# Sch_ma_Global.net
KiCad netlist of a schematic drawn in Altium Designer
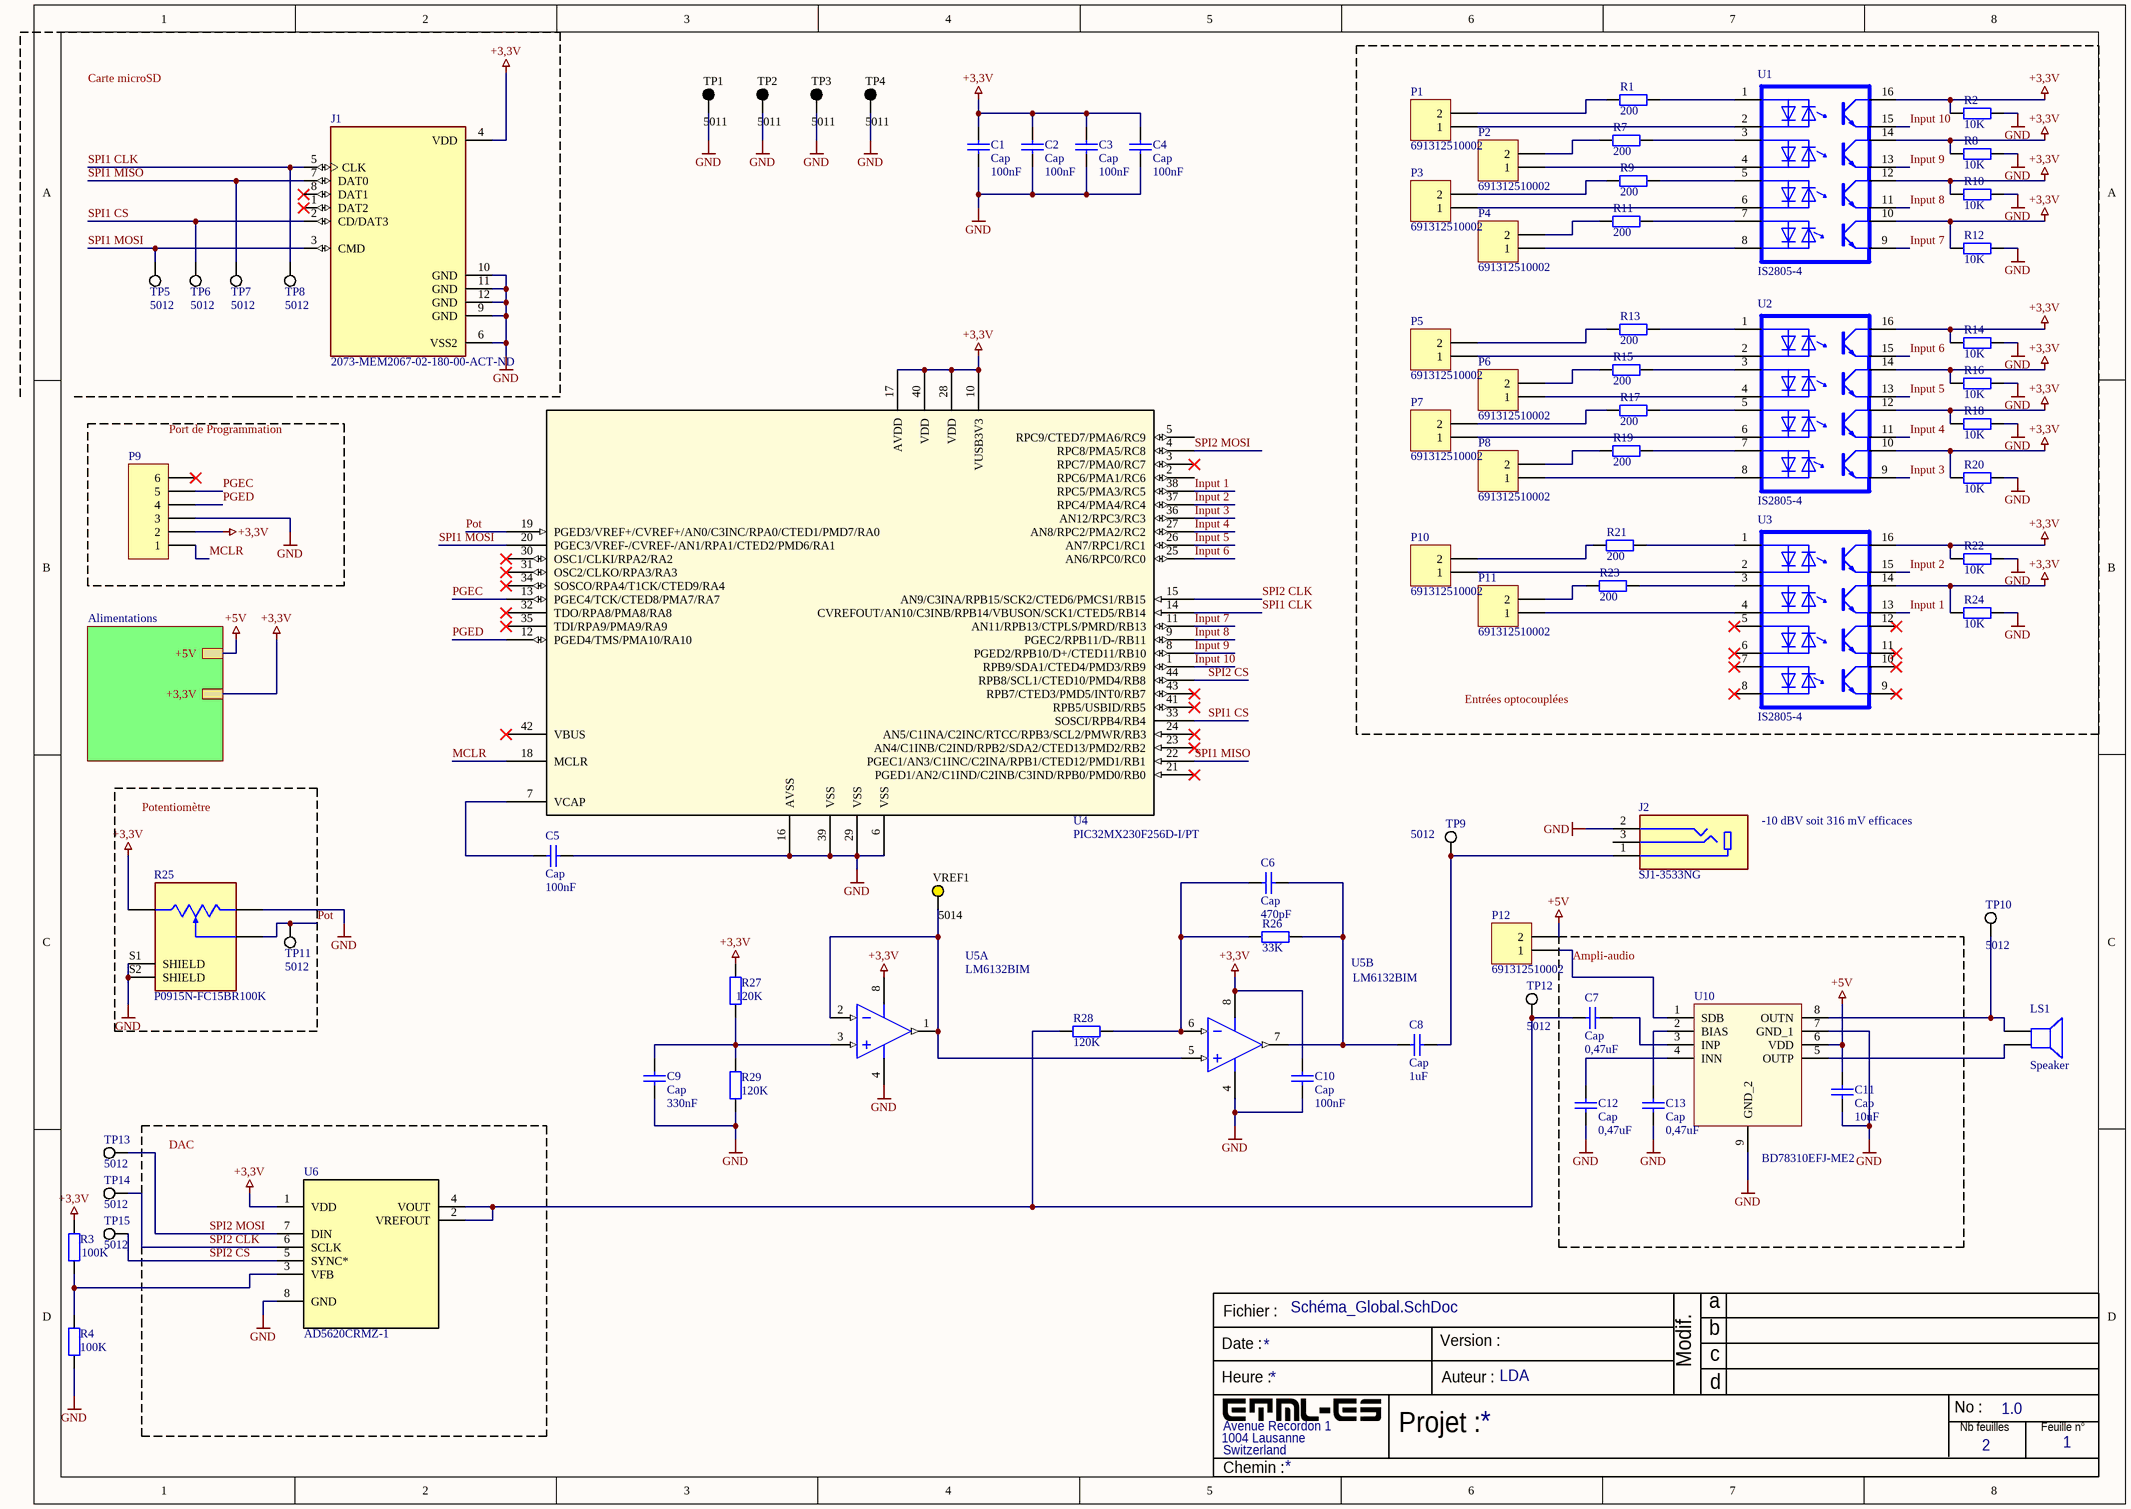
[diagram p0: Schéma_Global.SchDoc]

(export (version "E")
  (design (tool "Eeschema 10.0.6"))
  (components
    (comp (ref "C1")
      (value "Cap")
      (footprint "C0805")
      (description "Capacitor")
      (fields (field (name "ALTIUM_VALUE") "100nF") (field (name "PUBLISHER") "Altium Limited"))
      (libsource (lib "Miscellaneous Devices") (part "Cap"))
    )
    (comp (ref "C2")
      (value "Cap")
      (footprint "C0805")
      (description "Capacitor")
      (fields (field (name "ALTIUM_VALUE") "100nF") (field (name "PUBLISHER") "Altium Limited"))
      (libsource (lib "Miscellaneous Devices") (part "Cap"))
    )
    (comp (ref "C3")
      (value "Cap")
      (footprint "C0805")
      (description "Capacitor")
      (fields (field (name "ALTIUM_VALUE") "100nF") (field (name "PUBLISHER") "Altium Limited"))
      (libsource (lib "Miscellaneous Devices") (part "Cap"))
    )
    (comp (ref "C4")
      (value "Cap")
      (footprint "C0805")
      (description "Capacitor")
      (fields (field (name "ALTIUM_VALUE") "100nF") (field (name "PUBLISHER") "Altium Limited"))
      (libsource (lib "Miscellaneous Devices") (part "Cap"))
    )
    (comp (ref "C5")
      (value "Cap")
      (footprint "C0805")
      (description "Capacitor")
      (fields (field (name "ALTIUM_VALUE") "100nF") (field (name "PUBLISHER") "Altium Limited"))
      (libsource (lib "Miscellaneous Devices") (part "Cap"))
    )
    (comp (ref "C6")
      (value "Cap")
      (footprint "C0805")
      (description "Capacitor")
      (fields (field (name "ALTIUM_VALUE") "470pF") (field (name "PUBLISHER") "Altium Limited"))
      (libsource (lib "Miscellaneous Devices") (part "Cap"))
    )
    (comp (ref "C7")
      (value "Cap")
      (footprint "C0805")
      (description "Capacitor")
      (fields (field (name "ALTIUM_VALUE") "0,47uF") (field (name "PUBLISHER") "Altium Limited"))
      (libsource (lib "Miscellaneous Devices") (part "Cap"))
    )
    (comp (ref "C8")
      (value "Cap")
      (footprint "C0805")
      (description "Capacitor")
      (fields (field (name "ALTIUM_VALUE") "1uF") (field (name "PUBLISHER") "Altium Limited"))
      (libsource (lib "Miscellaneous Devices") (part "Cap"))
    )
    (comp (ref "C9")
      (value "Cap")
      (footprint "C0805")
      (description "Capacitor")
      (fields (field (name "ALTIUM_VALUE") "330nF") (field (name "PUBLISHER") "Altium Limited"))
      (libsource (lib "Miscellaneous Devices") (part "Cap"))
    )
    (comp (ref "C10")
      (value "Cap")
      (footprint "C0805")
      (description "Capacitor")
      (fields (field (name "ALTIUM_VALUE") "100nF") (field (name "PUBLISHER") "Altium Limited"))
      (libsource (lib "Miscellaneous Devices") (part "Cap"))
    )
    (comp (ref "C11")
      (value "Cap")
      (footprint "C0805")
      (description "Capacitor")
      (fields (field (name "ALTIUM_VALUE") "10uF") (field (name "PUBLISHER") "Altium Limited"))
      (libsource (lib "Miscellaneous Devices") (part "Cap"))
    )
    (comp (ref "C12")
      (value "Cap")
      (footprint "C0805")
      (description "Capacitor")
      (fields (field (name "ALTIUM_VALUE") "0,47uF") (field (name "PUBLISHER") "Altium Limited"))
      (libsource (lib "Miscellaneous Devices") (part "Cap"))
    )
    (comp (ref "C13")
      (value "Cap")
      (footprint "C0805")
      (description "Capacitor")
      (fields (field (name "ALTIUM_VALUE") "0,47uF") (field (name "PUBLISHER") "Altium Limited"))
      (libsource (lib "Miscellaneous Devices") (part "Cap"))
    )
    (comp (ref "J1")
      (value "2073-MEM2067-02-180-00-ACT-ND")
      (footprint "GCT_MEM2067-02-180-00-A_REVB")
      (description "2 In 1 Connector Sd+mmc")
      (fields (field (name "MP") "GMC020080HR") (field (name "MF") "Amphenol ICC (Commercial Products)"))
      (libsource (lib "2227_BoiteBruitage") (part "GMC020080HR"))
    )
    (comp (ref "J2")
      (value "SJ1-3533NG")
      (footprint "CUI_SJ1-3533NG")
      (description "3.5 mm Right-Angle Stereo Jack, 3 Pin PCB Mount, Isolated Ground")
      (fields (field (name "MF") "{'manufacturer': u'CUI'}"))
      (libsource (lib "2227_BoiteBruitage") (part "SJ1-3533NG"))
    )
    (comp (ref "LS1")
      (value "Speaker")
      (footprint "PIN2")
      (description "Loudspeaker")
      (fields (field (name "PUBLISHER") "Altium Limited"))
      (libsource (lib "Miscellaneous Devices") (part "Speaker"))
    )
    (comp (ref "P1")
      (value "691312510002")
      (footprint "691312710002")
      (description "Header, 2-Pin")
      (fields (field (name "PUBLISHER") "Altium Limited"))
      (libsource (lib "Miscellaneous Connectors") (part "MHDR1X2"))
    )
    (comp (ref "P2")
      (value "691312510002")
      (footprint "691312710002")
      (description "Header, 2-Pin")
      (fields (field (name "PUBLISHER") "Altium Limited"))
      (libsource (lib "Miscellaneous Connectors") (part "MHDR1X2"))
    )
    (comp (ref "P3")
      (value "691312510002")
      (footprint "691312710002")
      (description "Header, 2-Pin")
      (fields (field (name "PUBLISHER") "Altium Limited"))
      (libsource (lib "Miscellaneous Connectors") (part "MHDR1X2"))
    )
    (comp (ref "P4")
      (value "691312510002")
      (footprint "691312710002")
      (description "Header, 2-Pin")
      (fields (field (name "PUBLISHER") "Altium Limited"))
      (libsource (lib "Miscellaneous Connectors") (part "MHDR1X2"))
    )
    (comp (ref "P5")
      (value "691312510002")
      (footprint "691312710002")
      (description "Header, 2-Pin")
      (fields (field (name "PUBLISHER") "Altium Limited"))
      (libsource (lib "Miscellaneous Connectors") (part "MHDR1X2"))
    )
    (comp (ref "P6")
      (value "691312510002")
      (footprint "691312710002")
      (description "Header, 2-Pin")
      (fields (field (name "PUBLISHER") "Altium Limited"))
      (libsource (lib "Miscellaneous Connectors") (part "MHDR1X2"))
    )
    (comp (ref "P7")
      (value "691312510002")
      (footprint "691312710002")
      (description "Header, 2-Pin")
      (fields (field (name "PUBLISHER") "Altium Limited"))
      (libsource (lib "Miscellaneous Connectors") (part "MHDR1X2"))
    )
    (comp (ref "P8")
      (value "691312510002")
      (footprint "691312710002")
      (description "Header, 2-Pin")
      (fields (field (name "PUBLISHER") "Altium Limited"))
      (libsource (lib "Miscellaneous Connectors") (part "MHDR1X2"))
    )
    (comp (ref "P9")
      (value "76384-406LF")
      (footprint "HDR1X6")
      (description "Header, 6-Pin")
      (fields (field (name "PUBLISHER") "Altium Limited"))
      (libsource (lib "Miscellaneous Connectors") (part "Header 6"))
    )
    (comp (ref "P10")
      (value "691312510002")
      (footprint "691312710002")
      (description "Header, 2-Pin")
      (fields (field (name "PUBLISHER") "Altium Limited"))
      (libsource (lib "Miscellaneous Connectors") (part "MHDR1X2"))
    )
    (comp (ref "P11")
      (value "691312510002")
      (footprint "691312710002")
      (description "Header, 2-Pin")
      (fields (field (name "PUBLISHER") "Altium Limited"))
      (libsource (lib "Miscellaneous Connectors") (part "MHDR1X2"))
    )
    (comp (ref "P12")
      (value "691312510002")
      (footprint "MHDR1X2")
      (description "Header, 2-Pin")
      (fields (field (name "PUBLISHER") "Altium Limited"))
      (libsource (lib "Miscellaneous Connectors") (part "MHDR1X2"))
    )
    (comp (ref "R1")
      (value "200")
      (footprint "C1206")
      (description "Resistor")
      (fields (field (name "Comment") "Res2") (field (name "PUBLISHER") "Altium Limited"))
      (libsource (lib "Miscellaneous Devices") (part "Res2"))
    )
    (comp (ref "R2")
      (value "10K")
      (footprint "C1206")
      (description "Resistor")
      (fields (field (name "Comment") "Res2") (field (name "PUBLISHER") "Altium Limited"))
      (libsource (lib "Miscellaneous Devices") (part "Res2"))
    )
    (comp (ref "R3")
      (value "100K")
      (footprint "C1206")
      (description "Resistor")
      (fields (field (name "Comment") "Res2") (field (name "PUBLISHER") "Altium Limited"))
      (libsource (lib "") (part "Res2_1"))
    )
    (comp (ref "R4")
      (value "100K")
      (footprint "C1206")
      (description "Resistor")
      (fields (field (name "Comment") "Res2") (field (name "PUBLISHER") "Altium Limited"))
      (libsource (lib "") (part "Res2_1"))
    )
    (comp (ref "R7")
      (value "200")
      (footprint "C1206")
      (description "Resistor")
      (fields (field (name "Comment") "Res2") (field (name "PUBLISHER") "Altium Limited"))
      (libsource (lib "Miscellaneous Devices") (part "Res2"))
    )
    (comp (ref "R8")
      (value "10K")
      (footprint "C1206")
      (description "Resistor")
      (fields (field (name "Comment") "Res2") (field (name "PUBLISHER") "Altium Limited"))
      (libsource (lib "Miscellaneous Devices") (part "Res2"))
    )
    (comp (ref "R9")
      (value "200")
      (footprint "C1206")
      (description "Resistor")
      (fields (field (name "Comment") "Res2") (field (name "PUBLISHER") "Altium Limited"))
      (libsource (lib "Miscellaneous Devices") (part "Res2"))
    )
    (comp (ref "R10")
      (value "10K")
      (footprint "C1206")
      (description "Resistor")
      (fields (field (name "Comment") "Res2") (field (name "PUBLISHER") "Altium Limited"))
      (libsource (lib "Miscellaneous Devices") (part "Res2"))
    )
    (comp (ref "R11")
      (value "200")
      (footprint "C1206")
      (description "Resistor")
      (fields (field (name "Comment") "Res2") (field (name "PUBLISHER") "Altium Limited"))
      (libsource (lib "Miscellaneous Devices") (part "Res2"))
    )
    (comp (ref "R12")
      (value "10K")
      (footprint "C1206")
      (description "Resistor")
      (fields (field (name "Comment") "Res2") (field (name "PUBLISHER") "Altium Limited"))
      (libsource (lib "Miscellaneous Devices") (part "Res2"))
    )
    (comp (ref "R13")
      (value "200")
      (footprint "C1206")
      (description "Resistor")
      (fields (field (name "Comment") "Res2") (field (name "PUBLISHER") "Altium Limited"))
      (libsource (lib "Miscellaneous Devices") (part "Res2"))
    )
    (comp (ref "R14")
      (value "10K")
      (footprint "C1206")
      (description "Resistor")
      (fields (field (name "Comment") "Res2") (field (name "PUBLISHER") "Altium Limited"))
      (libsource (lib "Miscellaneous Devices") (part "Res2"))
    )
    (comp (ref "R15")
      (value "200")
      (footprint "C1206")
      (description "Resistor")
      (fields (field (name "Comment") "Res2") (field (name "PUBLISHER") "Altium Limited"))
      (libsource (lib "Miscellaneous Devices") (part "Res2"))
    )
    (comp (ref "R16")
      (value "10K")
      (footprint "C1206")
      (description "Resistor")
      (fields (field (name "Comment") "Res2") (field (name "PUBLISHER") "Altium Limited"))
      (libsource (lib "Miscellaneous Devices") (part "Res2"))
    )
    (comp (ref "R17")
      (value "200")
      (footprint "C1206")
      (description "Resistor")
      (fields (field (name "Comment") "Res2") (field (name "PUBLISHER") "Altium Limited"))
      (libsource (lib "Miscellaneous Devices") (part "Res2"))
    )
    (comp (ref "R18")
      (value "10K")
      (footprint "C1206")
      (description "Resistor")
      (fields (field (name "Comment") "Res2") (field (name "PUBLISHER") "Altium Limited"))
      (libsource (lib "Miscellaneous Devices") (part "Res2"))
    )
    (comp (ref "R19")
      (value "200")
      (footprint "C1206")
      (description "Resistor")
      (fields (field (name "Comment") "Res2") (field (name "PUBLISHER") "Altium Limited"))
      (libsource (lib "Miscellaneous Devices") (part "Res2"))
    )
    (comp (ref "R20")
      (value "10K")
      (footprint "C1206")
      (description "Resistor")
      (fields (field (name "Comment") "Res2") (field (name "PUBLISHER") "Altium Limited"))
      (libsource (lib "Miscellaneous Devices") (part "Res2"))
    )
    (comp (ref "R21")
      (value "200")
      (footprint "C1206")
      (description "Resistor")
      (fields (field (name "Comment") "Res2") (field (name "PUBLISHER") "Altium Limited"))
      (libsource (lib "Miscellaneous Devices") (part "Res2"))
    )
    (comp (ref "R22")
      (value "10K")
      (footprint "C1206")
      (description "Resistor")
      (fields (field (name "Comment") "Res2") (field (name "PUBLISHER") "Altium Limited"))
      (libsource (lib "Miscellaneous Devices") (part "Res2"))
    )
    (comp (ref "R23")
      (value "200")
      (footprint "C1206")
      (description "Resistor")
      (fields (field (name "Comment") "Res2") (field (name "PUBLISHER") "Altium Limited"))
      (libsource (lib "Miscellaneous Devices") (part "Res2"))
    )
    (comp (ref "R24")
      (value "10K")
      (footprint "C1206")
      (description "Resistor")
      (fields (field (name "Comment") "Res2") (field (name "PUBLISHER") "Altium Limited"))
      (libsource (lib "Miscellaneous Devices") (part "Res2"))
    )
    (comp (ref "R25")
      (value "P0915N-FC15BR100K")
      (footprint "TRIM_P0915N-FC15BR100K")
      (fields (field (name "MF") "BI Technologies (TT electronics)"))
      (libsource (lib "2227_BoiteBruitage") (part "P0915N-FC15BR100K"))
    )
    (comp (ref "R26")
      (value "33K")
      (footprint "C1206")
      (description "Resistor")
      (fields (field (name "Comment") "Res2") (field (name "PUBLISHER") "Altium Limited"))
      (libsource (lib "Miscellaneous Devices") (part "Res2"))
    )
    (comp (ref "R27")
      (value "120K")
      (footprint "C1206")
      (description "Resistor")
      (fields (field (name "Comment") "Res2") (field (name "PUBLISHER") "Altium Limited"))
      (libsource (lib "") (part "Res2_1"))
    )
    (comp (ref "R28")
      (value "120K")
      (footprint "C1206")
      (description "Resistor")
      (fields (field (name "Comment") "Res2") (field (name "PUBLISHER") "Altium Limited"))
      (libsource (lib "Miscellaneous Devices") (part "Res2"))
    )
    (comp (ref "R29")
      (value "120K")
      (footprint "C1206")
      (description "Resistor")
      (fields (field (name "Comment") "Res2") (field (name "PUBLISHER") "Altium Limited"))
      (libsource (lib "") (part "Res2_1"))
    )
    (comp (ref "TP1")
      (value "5011")
      (footprint "KSTN-5011_V")
      (description "Test Point, Black, Through Hole, RoHS, Bulk")
      (fields (field (name "MANUFACTURER") "Keystone"))
      (libsource (lib "Altium Content Vault") (part "TESTPOINT_BLACK"))
    )
    (comp (ref "TP2")
      (value "5011")
      (footprint "KSTN-5011_V")
      (description "Test Point, Black, Through Hole, RoHS, Bulk")
      (fields (field (name "MANUFACTURER") "Keystone"))
      (libsource (lib "Altium Content Vault") (part "TESTPOINT_BLACK"))
    )
    (comp (ref "TP3")
      (value "5011")
      (footprint "KSTN-5011_V")
      (description "Test Point, Black, Through Hole, RoHS, Bulk")
      (fields (field (name "MANUFACTURER") "Keystone"))
      (libsource (lib "Altium Content Vault") (part "TESTPOINT_BLACK"))
    )
    (comp (ref "TP4")
      (value "5011")
      (footprint "KSTN-5011_V")
      (description "Test Point, Black, Through Hole, RoHS, Bulk")
      (fields (field (name "MANUFACTURER") "Keystone"))
      (libsource (lib "Altium Content Vault") (part "TESTPOINT_BLACK"))
    )
    (comp (ref "TP5")
      (value "5012")
      (footprint "KSTN-5012_V")
      (description "Test Point, White, Through Hole, RoHS, Bulk")
      (fields (field (name "MANUFACTURER") "Keystone"))
      (libsource (lib "Altium Content Vault") (part "TESTPOINT_WHITE"))
    )
    (comp (ref "TP6")
      (value "5012")
      (footprint "KSTN-5012_V")
      (description "Test Point, White, Through Hole, RoHS, Bulk")
      (fields (field (name "MANUFACTURER") "Keystone"))
      (libsource (lib "Altium Content Vault") (part "TESTPOINT_WHITE"))
    )
    (comp (ref "TP7")
      (value "5012")
      (footprint "KSTN-5012_V")
      (description "Test Point, White, Through Hole, RoHS, Bulk")
      (fields (field (name "MANUFACTURER") "Keystone"))
      (libsource (lib "Altium Content Vault") (part "TESTPOINT_WHITE"))
    )
    (comp (ref "TP8")
      (value "5012")
      (footprint "KSTN-5012_V")
      (description "Test Point, White, Through Hole, RoHS, Bulk")
      (fields (field (name "MANUFACTURER") "Keystone"))
      (libsource (lib "Altium Content Vault") (part "TESTPOINT_WHITE"))
    )
    (comp (ref "TP9")
      (value "5012")
      (footprint "KSTN-5012_V")
      (description "Test Point, White, Through Hole, RoHS, Bulk")
      (fields (field (name "MANUFACTURER") "Keystone"))
      (libsource (lib "Altium Content Vault") (part "TESTPOINT_WHITE"))
    )
    (comp (ref "TP10")
      (value "5012")
      (footprint "KSTN-5012_V")
      (description "Test Point, White, Through Hole, RoHS, Bulk")
      (fields (field (name "MANUFACTURER") "Keystone"))
      (libsource (lib "Altium Content Vault") (part "TESTPOINT_WHITE"))
    )
    (comp (ref "TP11")
      (value "5012")
      (footprint "KSTN-5012_V")
      (description "Test Point, White, Through Hole, RoHS, Bulk")
      (fields (field (name "MANUFACTURER") "Keystone"))
      (libsource (lib "Altium Content Vault") (part "TESTPOINT_WHITE"))
    )
    (comp (ref "TP12")
      (value "5012")
      (footprint "KSTN-5012_V")
      (description "Test Point, White, Through Hole, RoHS, Bulk")
      (fields (field (name "MANUFACTURER") "Keystone"))
      (libsource (lib "Altium Content Vault") (part "TESTPOINT_WHITE"))
    )
    (comp (ref "TP13")
      (value "5012")
      (footprint "KSTN-5012_V")
      (description "Test Point, White, Through Hole, RoHS, Bulk")
      (fields (field (name "MANUFACTURER") "Keystone"))
      (libsource (lib "Altium Content Vault") (part "TESTPOINT_WHITE"))
    )
    (comp (ref "TP14")
      (value "5012")
      (footprint "KSTN-5012_V")
      (description "Test Point, White, Through Hole, RoHS, Bulk")
      (fields (field (name "MANUFACTURER") "Keystone"))
      (libsource (lib "Altium Content Vault") (part "TESTPOINT_WHITE"))
    )
    (comp (ref "TP15")
      (value "5012")
      (footprint "KSTN-5012_V")
      (description "Test Point, White, Through Hole, RoHS, Bulk")
      (fields (field (name "MANUFACTURER") "Keystone"))
      (libsource (lib "Altium Content Vault") (part "TESTPOINT_WHITE"))
    )
    (comp (ref "U1")
      (value "IS2805-4")
      (footprint "Opto_SOIC")
      (fields (field (name "MP") "VOS615A-1X001T"))
      (libsource (lib "2227_BoiteBruitage") (part "IS2805-4"))
    )
    (comp (ref "U2")
      (value "IS2805-4")
      (footprint "Opto_SOIC")
      (fields (field (name "MP") "VOS615A-1X001T"))
      (libsource (lib "2227_BoiteBruitage") (part "IS2805-4"))
    )
    (comp (ref "U3")
      (value "IS2805-4")
      (footprint "Opto_SOIC")
      (fields (field (name "MP") "VOS615A-1X001T"))
      (libsource (lib "2227_BoiteBruitage") (part "IS2805-4"))
    )
    (comp (ref "U4")
      (value "PIC32MX230F256D-I/PT")
      (footprint "TQFP44_PT_MCH")
      (description "No Description Available")
      (fields (field (name "COPYRIGHT") "Copyright (C) 2023 Ultra Librarian. All rights reserved."))
      (libsource (lib "2227_BoiteBruitage") (part "PIC32MX230F256D-I/PT"))
    )
    (comp (ref "U5")
      (value "LM6132BIM")
      (footprint "D0008A_N")
      (description "Dual Low Power 10 MHz Rail-to-Rail I/O Operational Amplifier, 8-pin Narrow SOIC")
      (fields (field (name "MANUFACTURER") "Texas Instruments"))
      (libsource (lib "Altium Content Vault") (part "AMP-OPA-LM6132-8"))
    )
    (comp (ref "U6")
      (value "AD5620CRMZ-1")
      (footprint "SOP65P490X110-8N")
      (description "Single, 12-Bit nanoDACÂ® with 5 ppm/Â°C On-Chip Reference in SOT-23")
      (fields (field (name "MF") "Analog Devices"))
      (libsource (lib "2227_BoiteBruitage") (part "AD5620CRMZ-1"))
    )
    (comp (ref "U10")
      (value "BD78310EFJ-ME2")
      (footprint "AOP_HASOP-J8")
      (description "1.2W MONAURAL SPEAKER AMPLIFIER")
      (fields (field (name "MOUSER PART NUMBER") "755-BD78310EFJ-ME2"))
      (libsource (lib "2227_BoiteBruitage") (part "BD78310EFJ-ME2"))
    )
    (comp (ref "VREF1")
      (value "5014")
      (footprint "KSTN-5014_V")
      (description "Test Point, Yellow, Through Hole, RoHS, Bulk")
      (fields (field (name "MANUFACTURER") "Keystone"))
      (libsource (lib "Altium Content Vault") (part "TESTPOINT_YELLOW"))
    )
  )
  (nets
    (net (code "1") (name "+3,3V") (class "Default")
      (node (ref "C1") (pin "1") (pinfunction "1_1") (pintype "passive"))
      (node (ref "C10") (pin "2") (pinfunction "2_2") (pintype "passive"))
      (node (ref "C2") (pin "1") (pinfunction "1_1") (pintype "passive"))
      (node (ref "C3") (pin "1") (pinfunction "1_1") (pintype "passive"))
      (node (ref "C4") (pin "1") (pinfunction "1_1") (pintype "passive"))
      (node (ref "J1") (pin "4") (pinfunction "VDD_4") (pintype "power_in"))
      (node (ref "P9") (pin "2") (pinfunction "2_2") (pintype "passive"))
      (node (ref "R10") (pin "1") (pinfunction "1_1") (pintype "passive"))
      (node (ref "R12") (pin "1") (pinfunction "1_1") (pintype "passive"))
      (node (ref "R14") (pin "1") (pinfunction "1_1") (pintype "passive"))
      (node (ref "R16") (pin "1") (pinfunction "1_1") (pintype "passive"))
      (node (ref "R18") (pin "1") (pinfunction "1_1") (pintype "passive"))
      (node (ref "R2") (pin "1") (pinfunction "1_1") (pintype "passive"))
      (node (ref "R20") (pin "1") (pinfunction "1_1") (pintype "passive"))
      (node (ref "R22") (pin "1") (pinfunction "1_1") (pintype "passive"))
      (node (ref "R24") (pin "1") (pinfunction "1_1") (pintype "passive"))
      (node (ref "R25") (pin "1") (pinfunction "1_1") (pintype "passive"))
      (node (ref "R27") (pin "2") (pinfunction "2_2") (pintype "passive"))
      (node (ref "R3") (pin "2") (pinfunction "2_2") (pintype "passive"))
      (node (ref "R8") (pin "1") (pinfunction "1_1") (pintype "passive"))
      (node (ref "U1") (pin "10") (pinfunction "CO_10") (pintype "passive"))
      (node (ref "U1") (pin "12") (pinfunction "CO_12") (pintype "passive"))
      (node (ref "U1") (pin "14") (pinfunction "CO_14") (pintype "passive"))
      (node (ref "U1") (pin "16") (pinfunction "CO_16") (pintype "passive"))
      (node (ref "U2") (pin "10") (pinfunction "CO_10") (pintype "passive"))
      (node (ref "U2") (pin "12") (pinfunction "CO_12") (pintype "passive"))
      (node (ref "U2") (pin "14") (pinfunction "CO_14") (pintype "passive"))
      (node (ref "U2") (pin "16") (pinfunction "CO_16") (pintype "passive"))
      (node (ref "U3") (pin "14") (pinfunction "CO_14") (pintype "passive"))
      (node (ref "U3") (pin "16") (pinfunction "CO_16") (pintype "passive"))
      (node (ref "U4") (pin "10") (pinfunction "VUSB3V3_10") (pintype "power_in"))
      (node (ref "U4") (pin "17") (pinfunction "AVDD_17") (pintype "power_in"))
      (node (ref "U4") (pin "28") (pinfunction "VDD_28") (pintype "power_in"))
      (node (ref "U4") (pin "40") (pinfunction "VDD_40") (pintype "power_in"))
      (node (ref "U5") (pin "8") (pinfunction "V+_8") (pintype "power_in"))
      (node (ref "U6") (pin "1") (pinfunction "VDD_1") (pintype "power_in"))
    )
    (net (code "2") (name "+5V") (class "Default")
      (node (ref "C11") (pin "1") (pinfunction "1_1") (pintype "passive"))
      (node (ref "P12") (pin "2") (pinfunction "2_2") (pintype "passive"))
      (node (ref "U10") (pin "6") (pinfunction "VDD_6") (pintype "passive"))
    )
    (net (code "3") (name "/Input 1") (class "Default")
      (node (ref "U3") (pin "13") (pinfunction "E_13") (pintype "passive"))
      (node (ref "U4") (pin "38") (pinfunction "RPC5/PMA3/RC5_38") (pintype "bidirectional"))
    )
    (net (code "4") (name "/Input 2") (class "Default")
      (node (ref "U3") (pin "15") (pinfunction "E_15") (pintype "passive"))
      (node (ref "U4") (pin "37") (pinfunction "RPC4/PMA4/RC4_37") (pintype "bidirectional"))
    )
    (net (code "5") (name "/Input 3") (class "Default")
      (node (ref "U2") (pin "9") (pinfunction "E_9") (pintype "passive"))
      (node (ref "U4") (pin "36") (pinfunction "AN12/RPC3/RC3_36") (pintype "bidirectional"))
    )
    (net (code "6") (name "/Input 4") (class "Default")
      (node (ref "U2") (pin "11") (pinfunction "E_11") (pintype "passive"))
      (node (ref "U4") (pin "27") (pinfunction "AN8/RPC2/PMA2/RC2_27") (pintype "bidirectional"))
    )
    (net (code "7") (name "/Input 5") (class "Default")
      (node (ref "U2") (pin "13") (pinfunction "E_13") (pintype "passive"))
      (node (ref "U4") (pin "26") (pinfunction "AN7/RPC1/RC1_26") (pintype "bidirectional"))
    )
    (net (code "8") (name "/Input 6") (class "Default")
      (node (ref "U2") (pin "15") (pinfunction "E_15") (pintype "passive"))
      (node (ref "U4") (pin "25") (pinfunction "AN6/RPC0/RC0_25") (pintype "bidirectional"))
    )
    (net (code "9") (name "/Input 7") (class "Default")
      (node (ref "U1") (pin "9") (pinfunction "E_9") (pintype "passive"))
      (node (ref "U4") (pin "11") (pinfunction "AN11/RPB13/CTPLS/PMRD/RB13_11") (pintype "bidirectional"))
    )
    (net (code "10") (name "/Input 8") (class "Default")
      (node (ref "U1") (pin "11") (pinfunction "E_11") (pintype "passive"))
      (node (ref "U4") (pin "9") (pinfunction "PGEC2/RPB11/D-/RB11_9") (pintype "bidirectional"))
    )
    (net (code "11") (name "/Input 9") (class "Default")
      (node (ref "U1") (pin "13") (pinfunction "E_13") (pintype "passive"))
      (node (ref "U4") (pin "8") (pinfunction "PGED2/RPB10/D+/CTED11/RB10_8") (pintype "bidirectional"))
    )
    (net (code "12") (name "/Input 10") (class "Default")
      (node (ref "U1") (pin "15") (pinfunction "E_15") (pintype "passive"))
      (node (ref "U4") (pin "1") (pinfunction "RPB9/SDA1/CTED4/PMD3/RB9_1") (pintype "bidirectional"))
    )
    (net (code "13") (name "/MCLR") (class "Default")
      (node (ref "P9") (pin "1") (pinfunction "1_1") (pintype "passive"))
      (node (ref "U4") (pin "18") (pinfunction "MCLR_18") (pintype "passive"))
    )
    (net (code "14") (name "/PGEC") (class "Default")
      (node (ref "P9") (pin "5") (pinfunction "5_5") (pintype "passive"))
      (node (ref "U4") (pin "13") (pinfunction "PGEC4/TCK/CTED8/PMA7/RA7_13") (pintype "bidirectional"))
    )
    (net (code "15") (name "/PGED") (class "Default")
      (node (ref "P9") (pin "4") (pinfunction "4_4") (pintype "passive"))
      (node (ref "U4") (pin "12") (pinfunction "PGED4/TMS/PMA10/RA10_12") (pintype "bidirectional"))
    )
    (net (code "16") (name "/Pot") (class "Default")
      (node (ref "R25") (pin "2") (pinfunction "2_2") (pintype "passive"))
      (node (ref "TP11") (pin "1") (pinfunction "1_1") (pintype "passive"))
      (node (ref "U4") (pin "19") (pinfunction "PGED3/VREF+/CVREF+/AN0/C3INC/RPA0/CTED1/PMD7/RA0_19") (pintype "input"))
    )
    (net (code "17") (name "/SPI1 CLK") (class "Default")
      (node (ref "J1") (pin "5") (pinfunction "CLK_5") (pintype "bidirectional"))
      (node (ref "TP8") (pin "1") (pinfunction "1_1") (pintype "passive"))
      (node (ref "U4") (pin "14") (pinfunction "CVREFOUT/AN10/C3INB/RPB14/VBUSON/SCK1/CTED5/RB14_14") (pintype "input"))
    )
    (net (code "18") (name "/SPI1 CS") (class "Default")
      (node (ref "J1") (pin "2") (pinfunction "CD/DAT3_2") (pintype "bidirectional"))
      (node (ref "TP6") (pin "1") (pinfunction "1_1") (pintype "passive"))
      (node (ref "U4") (pin "33") (pinfunction "SOSCI/RPB4/RB4_33") (pintype "passive"))
    )
    (net (code "19") (name "/SPI1 MISO") (class "Default")
      (node (ref "J1") (pin "7") (pinfunction "DAT0_7") (pintype "bidirectional"))
      (node (ref "TP7") (pin "1") (pinfunction "1_1") (pintype "passive"))
      (node (ref "U4") (pin "22") (pinfunction "PGEC1/AN3/C1INC/C2INA/RPB1/CTED12/PMD1/RB1_22") (pintype "input"))
    )
    (net (code "20") (name "/SPI1 MOSI") (class "Default")
      (node (ref "J1") (pin "3") (pinfunction "CMD_3") (pintype "bidirectional"))
      (node (ref "TP5") (pin "1") (pinfunction "1_1") (pintype "passive"))
      (node (ref "U4") (pin "20") (pinfunction "PGEC3/VREF-/CVREF-/AN1/RPA1/CTED2/PMD6/RA1_20") (pintype "power_in"))
    )
    (net (code "21") (name "/SPI2 CLK") (class "Default")
      (node (ref "TP14") (pin "1") (pinfunction "1_1") (pintype "passive"))
      (node (ref "U4") (pin "15") (pinfunction "AN9/C3INA/RPB15/SCK2/CTED6/PMCS1/RB15_15") (pintype "input"))
      (node (ref "U6") (pin "6") (pinfunction "SCLK_6") (pintype "passive"))
    )
    (net (code "22") (name "/SPI2 CS") (class "Default")
      (node (ref "TP15") (pin "1") (pinfunction "1_1") (pintype "passive"))
      (node (ref "U4") (pin "44") (pinfunction "RPB8/SCL1/CTED10/PMD4/RB8_44") (pintype "bidirectional"))
      (node (ref "U6") (pin "5") (pinfunction "SYNC*_5") (pintype "passive"))
    )
    (net (code "23") (name "/SPI2 MOSI") (class "Default")
      (node (ref "TP13") (pin "1") (pinfunction "1_1") (pintype "passive"))
      (node (ref "U4") (pin "4") (pinfunction "RPC8/PMA5/RC8_4") (pintype "bidirectional"))
      (node (ref "U6") (pin "7") (pinfunction "DIN_7") (pintype "passive"))
    )
    (net (code "24") (name "GND") (class "Default")
      (node (ref "C1") (pin "2") (pinfunction "2_2") (pintype "passive"))
      (node (ref "C10") (pin "1") (pinfunction "1_1") (pintype "passive"))
      (node (ref "C11") (pin "2") (pinfunction "2_2") (pintype "passive"))
      (node (ref "C12") (pin "1") (pinfunction "1_1") (pintype "passive"))
      (node (ref "C13") (pin "1") (pinfunction "1_1") (pintype "passive"))
      (node (ref "C2") (pin "2") (pinfunction "2_2") (pintype "passive"))
      (node (ref "C3") (pin "2") (pinfunction "2_2") (pintype "passive"))
      (node (ref "C4") (pin "2") (pinfunction "2_2") (pintype "passive"))
      (node (ref "C5") (pin "1") (pinfunction "1_1") (pintype "passive"))
      (node (ref "C9") (pin "1") (pinfunction "1_1") (pintype "passive"))
      (node (ref "J1") (pin "10") (pinfunction "GND_10") (pintype "power_in"))
      (node (ref "J1") (pin "11") (pinfunction "GND_11") (pintype "power_in"))
      (node (ref "J1") (pin "12") (pinfunction "GND_12") (pintype "power_in"))
      (node (ref "J1") (pin "6") (pinfunction "VSS2_6") (pintype "power_in"))
      (node (ref "J1") (pin "9") (pinfunction "GND_9") (pintype "power_in"))
      (node (ref "J2") (pin "2") (pinfunction "2_2") (pintype "passive"))
      (node (ref "P9") (pin "3") (pinfunction "3_3") (pintype "passive"))
      (node (ref "R10") (pin "2") (pinfunction "2_2") (pintype "passive"))
      (node (ref "R12") (pin "2") (pinfunction "2_2") (pintype "passive"))
      (node (ref "R14") (pin "2") (pinfunction "2_2") (pintype "passive"))
      (node (ref "R16") (pin "2") (pinfunction "2_2") (pintype "passive"))
      (node (ref "R18") (pin "2") (pinfunction "2_2") (pintype "passive"))
      (node (ref "R2") (pin "2") (pinfunction "2_2") (pintype "passive"))
      (node (ref "R20") (pin "2") (pinfunction "2_2") (pintype "passive"))
      (node (ref "R22") (pin "2") (pinfunction "2_2") (pintype "passive"))
      (node (ref "R24") (pin "2") (pinfunction "2_2") (pintype "passive"))
      (node (ref "R25") (pin "3") (pinfunction "3_3") (pintype "passive"))
      (node (ref "R25") (pin "S1") (pinfunction "SHIELD_S1") (pintype "passive"))
      (node (ref "R25") (pin "S2") (pinfunction "SHIELD_S2") (pintype "passive"))
      (node (ref "R29") (pin "1") (pinfunction "1_1") (pintype "passive"))
      (node (ref "R4") (pin "1") (pinfunction "1_1") (pintype "passive"))
      (node (ref "R8") (pin "2") (pinfunction "2_2") (pintype "passive"))
      (node (ref "TP1") (pin "1") (pinfunction "1_1") (pintype "passive"))
      (node (ref "TP2") (pin "1") (pinfunction "1_1") (pintype "passive"))
      (node (ref "TP3") (pin "1") (pinfunction "1_1") (pintype "passive"))
      (node (ref "TP4") (pin "1") (pinfunction "1_1") (pintype "passive"))
      (node (ref "U10") (pin "7") (pinfunction "GND_1_7") (pintype "passive"))
      (node (ref "U10") (pin "9") (pinfunction "GND_2_9") (pintype "passive"))
      (node (ref "U4") (pin "16") (pinfunction "AVSS_16") (pintype "passive"))
      (node (ref "U4") (pin "29") (pinfunction "VSS_29") (pintype "passive"))
      (node (ref "U4") (pin "39") (pinfunction "VSS_39") (pintype "passive"))
      (node (ref "U4") (pin "6") (pinfunction "VSS_6") (pintype "passive"))
      (node (ref "U5") (pin "4") (pinfunction "V-_4") (pintype "power_in"))
      (node (ref "U6") (pin "8") (pinfunction "GND_8") (pintype "passive"))
    )
    (net (code "25") (name "Net-(C8-Pad1)") (class "Default")
      (node (ref "C8") (pin "1") (pinfunction "1_1") (pintype "passive"))
      (node (ref "J2") (pin "1") (pinfunction "1_1") (pintype "passive"))
      (node (ref "TP9") (pin "1") (pinfunction "1_1") (pintype "passive"))
    )
    (net (code "26") (name "Net-(P1-Pad1)") (class "Default")
      (node (ref "P1") (pin "1") (pinfunction "1_1") (pintype "passive"))
      (node (ref "U1") (pin "2") (pinfunction "C_2") (pintype "passive"))
    )
    (net (code "27") (name "Net-(P1-Pad2)") (class "Default")
      (node (ref "P1") (pin "2") (pinfunction "2_2") (pintype "passive"))
      (node (ref "R1") (pin "1") (pinfunction "1_1") (pintype "passive"))
    )
    (net (code "28") (name "Net-(P2-Pad1)") (class "Default")
      (node (ref "P2") (pin "1") (pinfunction "1_1") (pintype "passive"))
      (node (ref "U1") (pin "4") (pinfunction "C_4") (pintype "passive"))
    )
    (net (code "29") (name "Net-(P2-Pad2)") (class "Default")
      (node (ref "P2") (pin "2") (pinfunction "2_2") (pintype "passive"))
      (node (ref "R7") (pin "1") (pinfunction "1_1") (pintype "passive"))
    )
    (net (code "30") (name "Net-(P3-Pad1)") (class "Default")
      (node (ref "P3") (pin "1") (pinfunction "1_1") (pintype "passive"))
      (node (ref "U1") (pin "6") (pinfunction "C_6") (pintype "passive"))
    )
    (net (code "31") (name "Net-(P3-Pad2)") (class "Default")
      (node (ref "P3") (pin "2") (pinfunction "2_2") (pintype "passive"))
      (node (ref "R9") (pin "1") (pinfunction "1_1") (pintype "passive"))
    )
    (net (code "32") (name "Net-(P4-Pad1)") (class "Default")
      (node (ref "P4") (pin "1") (pinfunction "1_1") (pintype "passive"))
      (node (ref "U1") (pin "8") (pinfunction "C_8") (pintype "passive"))
    )
    (net (code "33") (name "Net-(P4-Pad2)") (class "Default")
      (node (ref "P4") (pin "2") (pinfunction "2_2") (pintype "passive"))
      (node (ref "R11") (pin "1") (pinfunction "1_1") (pintype "passive"))
    )
    (net (code "34") (name "Net-(P5-Pad1)") (class "Default")
      (node (ref "P5") (pin "1") (pinfunction "1_1") (pintype "passive"))
      (node (ref "U2") (pin "2") (pinfunction "C_2") (pintype "passive"))
    )
    (net (code "35") (name "Net-(P5-Pad2)") (class "Default")
      (node (ref "P5") (pin "2") (pinfunction "2_2") (pintype "passive"))
      (node (ref "R13") (pin "1") (pinfunction "1_1") (pintype "passive"))
    )
    (net (code "36") (name "Net-(P6-Pad1)") (class "Default")
      (node (ref "P6") (pin "1") (pinfunction "1_1") (pintype "passive"))
      (node (ref "U2") (pin "4") (pinfunction "C_4") (pintype "passive"))
    )
    (net (code "37") (name "Net-(P6-Pad2)") (class "Default")
      (node (ref "P6") (pin "2") (pinfunction "2_2") (pintype "passive"))
      (node (ref "R15") (pin "1") (pinfunction "1_1") (pintype "passive"))
    )
    (net (code "38") (name "Net-(P7-Pad1)") (class "Default")
      (node (ref "P7") (pin "1") (pinfunction "1_1") (pintype "passive"))
      (node (ref "U2") (pin "6") (pinfunction "C_6") (pintype "passive"))
    )
    (net (code "39") (name "Net-(P7-Pad2)") (class "Default")
      (node (ref "P7") (pin "2") (pinfunction "2_2") (pintype "passive"))
      (node (ref "R17") (pin "1") (pinfunction "1_1") (pintype "passive"))
    )
    (net (code "40") (name "Net-(P8-Pad1)") (class "Default")
      (node (ref "P8") (pin "1") (pinfunction "1_1") (pintype "passive"))
      (node (ref "U2") (pin "8") (pinfunction "C_8") (pintype "passive"))
    )
    (net (code "41") (name "Net-(P8-Pad2)") (class "Default")
      (node (ref "P8") (pin "2") (pinfunction "2_2") (pintype "passive"))
      (node (ref "R19") (pin "1") (pinfunction "1_1") (pintype "passive"))
    )
    (net (code "42") (name "Net-(P10-Pad1)") (class "Default")
      (node (ref "P10") (pin "1") (pinfunction "1_1") (pintype "passive"))
      (node (ref "U3") (pin "2") (pinfunction "C_2") (pintype "passive"))
    )
    (net (code "43") (name "Net-(P10-Pad2)") (class "Default")
      (node (ref "P10") (pin "2") (pinfunction "2_2") (pintype "passive"))
      (node (ref "R21") (pin "1") (pinfunction "1_1") (pintype "passive"))
    )
    (net (code "44") (name "Net-(P11-Pad1)") (class "Default")
      (node (ref "P11") (pin "1") (pinfunction "1_1") (pintype "passive"))
      (node (ref "U3") (pin "4") (pinfunction "C_4") (pintype "passive"))
    )
    (net (code "45") (name "Net-(P11-Pad2)") (class "Default")
      (node (ref "P11") (pin "2") (pinfunction "2_2") (pintype "passive"))
      (node (ref "R23") (pin "1") (pinfunction "1_1") (pintype "passive"))
    )
    (net (code "46") (name "Net-(R1-Pad2)") (class "Default")
      (node (ref "R1") (pin "2") (pinfunction "2_2") (pintype "passive"))
      (node (ref "U1") (pin "1") (pinfunction "A_1") (pintype "passive"))
    )
    (net (code "47") (name "Net-(R7-Pad2)") (class "Default")
      (node (ref "R7") (pin "2") (pinfunction "2_2") (pintype "passive"))
      (node (ref "U1") (pin "3") (pinfunction "A_3") (pintype "passive"))
    )
    (net (code "48") (name "Net-(R9-Pad2)") (class "Default")
      (node (ref "R9") (pin "2") (pinfunction "2_2") (pintype "passive"))
      (node (ref "U1") (pin "5") (pinfunction "A_5") (pintype "passive"))
    )
    (net (code "49") (name "Net-(R11-Pad2)") (class "Default")
      (node (ref "R11") (pin "2") (pinfunction "2_2") (pintype "passive"))
      (node (ref "U1") (pin "7") (pinfunction "A_7") (pintype "passive"))
    )
    (net (code "50") (name "Net-(R13-Pad2)") (class "Default")
      (node (ref "R13") (pin "2") (pinfunction "2_2") (pintype "passive"))
      (node (ref "U2") (pin "1") (pinfunction "A_1") (pintype "passive"))
    )
    (net (code "51") (name "Net-(R15-Pad2)") (class "Default")
      (node (ref "R15") (pin "2") (pinfunction "2_2") (pintype "passive"))
      (node (ref "U2") (pin "3") (pinfunction "A_3") (pintype "passive"))
    )
    (net (code "52") (name "Net-(R17-Pad2)") (class "Default")
      (node (ref "R17") (pin "2") (pinfunction "2_2") (pintype "passive"))
      (node (ref "U2") (pin "5") (pinfunction "A_5") (pintype "passive"))
    )
    (net (code "53") (name "Net-(R19-Pad2)") (class "Default")
      (node (ref "R19") (pin "2") (pinfunction "2_2") (pintype "passive"))
      (node (ref "U2") (pin "7") (pinfunction "A_7") (pintype "passive"))
    )
    (net (code "54") (name "Net-(R21-Pad2)") (class "Default")
      (node (ref "R21") (pin "2") (pinfunction "2_2") (pintype "passive"))
      (node (ref "U3") (pin "1") (pinfunction "A_1") (pintype "passive"))
    )
    (net (code "55") (name "Net-(R23-Pad2)") (class "Default")
      (node (ref "R23") (pin "2") (pinfunction "2_2") (pintype "passive"))
      (node (ref "U3") (pin "3") (pinfunction "A_3") (pintype "passive"))
    )
    (net (code "56") (name "Net-(U4-VCAP)") (class "Default")
      (node (ref "C5") (pin "2") (pinfunction "2_2") (pintype "passive"))
      (node (ref "U4") (pin "7") (pinfunction "VCAP_7") (pintype "power_in"))
    )
    (net (code "57") (name "Net-(U5A-INA+)") (class "Default")
      (node (ref "C9") (pin "2") (pinfunction "2_2") (pintype "passive"))
      (node (ref "R27") (pin "1") (pinfunction "1_1") (pintype "passive"))
      (node (ref "R29") (pin "2") (pinfunction "2_2") (pintype "passive"))
      (node (ref "U5") (pin "3") (pinfunction "INA+_3") (pintype "input"))
    )
    (net (code "58") (name "Net-(U5A-INA-)") (class "Default")
      (node (ref "U5") (pin "1") (pinfunction "OUTA_1") (pintype "output"))
      (node (ref "U5") (pin "2") (pinfunction "INA-_2") (pintype "input"))
      (node (ref "U5") (pin "5") (pinfunction "INB+_5") (pintype "input"))
      (node (ref "VREF1") (pin "1") (pinfunction "1_1") (pintype "passive"))
    )
    (net (code "59") (name "Net-(U5B-INB-)") (class "Default")
      (node (ref "C6") (pin "2") (pinfunction "2_2") (pintype "passive"))
      (node (ref "R26") (pin "1") (pinfunction "1_1") (pintype "passive"))
      (node (ref "R28") (pin "2") (pinfunction "2_2") (pintype "passive"))
      (node (ref "U5") (pin "6") (pinfunction "INB-_6") (pintype "input"))
    )
    (net (code "60") (name "Net-(U5B-OUTB)") (class "Default")
      (node (ref "C6") (pin "1") (pinfunction "1_1") (pintype "passive"))
      (node (ref "C8") (pin "2") (pinfunction "2_2") (pintype "passive"))
      (node (ref "R26") (pin "2") (pinfunction "2_2") (pintype "passive"))
      (node (ref "U5") (pin "7") (pinfunction "OUTB_7") (pintype "output"))
    )
    (net (code "61") (name "Net-(U6-VFB)") (class "Default")
      (node (ref "R3") (pin "1") (pinfunction "1_1") (pintype "passive"))
      (node (ref "R4") (pin "2") (pinfunction "2_2") (pintype "passive"))
      (node (ref "U6") (pin "3") (pinfunction "VFB_3") (pintype "passive"))
    )
    (net (code "62") (name "Net-(U6-VOUT)") (class "Default")
      (node (ref "C7") (pin "2") (pinfunction "2_2") (pintype "passive"))
      (node (ref "R28") (pin "1") (pinfunction "1_1") (pintype "passive"))
      (node (ref "TP12") (pin "1") (pinfunction "1_1") (pintype "passive"))
      (node (ref "U6") (pin "2") (pinfunction "VREFOUT_2") (pintype "passive"))
      (node (ref "U6") (pin "4") (pinfunction "VOUT_4") (pintype "passive"))
    )
    (net (code "63") (name "Net-(U10-BIAS)") (class "Default")
      (node (ref "C13") (pin "2") (pinfunction "2_2") (pintype "passive"))
      (node (ref "U10") (pin "2") (pinfunction "BIAS_2") (pintype "passive"))
    )
    (net (code "64") (name "Net-(U10-INN)") (class "Default")
      (node (ref "C12") (pin "2") (pinfunction "2_2") (pintype "passive"))
      (node (ref "U10") (pin "4") (pinfunction "INN_4") (pintype "passive"))
    )
    (net (code "65") (name "Net-(U10-INP)") (class "Default")
      (node (ref "C7") (pin "1") (pinfunction "1_1") (pintype "passive"))
      (node (ref "U10") (pin "3") (pinfunction "INP_3") (pintype "passive"))
    )
    (net (code "66") (name "Net-(U10-OUTN)") (class "Default")
      (node (ref "LS1") (pin "1") (pinfunction "1_1") (pintype "passive"))
      (node (ref "TP10") (pin "1") (pinfunction "1_1") (pintype "passive"))
      (node (ref "U10") (pin "8") (pinfunction "OUTN_8") (pintype "passive"))
    )
    (net (code "67") (name "Net-(U10-OUTP)") (class "Default")
      (node (ref "LS1") (pin "2") (pinfunction "2_2") (pintype "passive"))
      (node (ref "U10") (pin "5") (pinfunction "OUTP_5") (pintype "passive"))
    )
    (net (code "68") (name "Net-(U10-SDB)") (class "Default")
      (node (ref "P12") (pin "1") (pinfunction "1_1") (pintype "passive"))
      (node (ref "U10") (pin "1") (pinfunction "SDB_1") (pintype "passive"))
    )
    (net (code "69") (name "unconnected-(J1-DAT1-Pad8)") (class "Default")
      (node (ref "J1") (pin "8") (pinfunction "DAT1_8") (pintype "bidirectional+no_connect"))
    )
    (net (code "70") (name "unconnected-(J1-DAT2-Pad1)") (class "Default")
      (node (ref "J1") (pin "1") (pinfunction "DAT2_1") (pintype "bidirectional+no_connect"))
    )
    (net (code "71") (name "unconnected-(J2-Pad3)") (class "Default")
      (node (ref "J2") (pin "3") (pinfunction "3_3") (pintype "passive"))
    )
    (net (code "72") (name "unconnected-(P9-Pad6)") (class "Default")
      (node (ref "P9") (pin "6") (pinfunction "6_6") (pintype "passive+no_connect"))
    )
    (net (code "73") (name "unconnected-(U3-A-Pad5)") (class "Default")
      (node (ref "U3") (pin "5") (pinfunction "A_5") (pintype "passive+no_connect"))
    )
    (net (code "74") (name "unconnected-(U3-A-Pad7)") (class "Default")
      (node (ref "U3") (pin "7") (pinfunction "A_7") (pintype "passive+no_connect"))
    )
    (net (code "75") (name "unconnected-(U3-C-Pad6)") (class "Default")
      (node (ref "U3") (pin "6") (pinfunction "C_6") (pintype "passive+no_connect"))
    )
    (net (code "76") (name "unconnected-(U3-C-Pad8)") (class "Default")
      (node (ref "U3") (pin "8") (pinfunction "C_8") (pintype "passive+no_connect"))
    )
    (net (code "77") (name "unconnected-(U3-CO-Pad10)") (class "Default")
      (node (ref "U3") (pin "10") (pinfunction "CO_10") (pintype "passive+no_connect"))
    )
    (net (code "78") (name "unconnected-(U3-CO-Pad12)") (class "Default")
      (node (ref "U3") (pin "12") (pinfunction "CO_12") (pintype "passive+no_connect"))
    )
    (net (code "79") (name "unconnected-(U3-E-Pad9)") (class "Default")
      (node (ref "U3") (pin "9") (pinfunction "E_9") (pintype "passive+no_connect"))
    )
    (net (code "80") (name "unconnected-(U3-E-Pad11)") (class "Default")
      (node (ref "U3") (pin "11") (pinfunction "E_11") (pintype "passive+no_connect"))
    )
    (net (code "81") (name "unconnected-(U4-AN4{slash}C1INB{slash}C2IND{slash}RPB2{slash}SDA2{slash}CTED13{slash}PMD2{slash}RB2-Pad23)") (class "Default")
      (node (ref "U4") (pin "23") (pinfunction "AN4/C1INB/C2IND/RPB2/SDA2/CTED13/PMD2/RB2_23") (pintype "input+no_connect"))
    )
    (net (code "82") (name "unconnected-(U4-AN5{slash}C1INA{slash}C2INC{slash}RTCC{slash}RPB3{slash}SCL2{slash}PMWR{slash}RB3-Pad24)") (class "Default")
      (node (ref "U4") (pin "24") (pinfunction "AN5/C1INA/C2INC/RTCC/RPB3/SCL2/PMWR/RB3_24") (pintype "input+no_connect"))
    )
    (net (code "83") (name "unconnected-(U4-OSC1{slash}CLKI{slash}RPA2{slash}RA2-Pad30)") (class "Default")
      (node (ref "U4") (pin "30") (pinfunction "OSC1/CLKI/RPA2/RA2_30") (pintype "bidirectional+no_connect"))
    )
    (net (code "84") (name "unconnected-(U4-OSC2{slash}CLKO{slash}RPA3{slash}RA3-Pad31)") (class "Default")
      (node (ref "U4") (pin "31") (pinfunction "OSC2/CLKO/RPA3/RA3_31") (pintype "bidirectional+no_connect"))
    )
    (net (code "85") (name "unconnected-(U4-PGED1{slash}AN2{slash}C1IND{slash}C2INB{slash}C3IND{slash}RPB0{slash}PMD0{slash}RB0-Pad21)") (class "Default")
      (node (ref "U4") (pin "21") (pinfunction "PGED1/AN2/C1IND/C2INB/C3IND/RPB0/PMD0/RB0_21") (pintype "input+no_connect"))
    )
    (net (code "86") (name "unconnected-(U4-RPB5{slash}USBID{slash}RB5-Pad41)") (class "Default")
      (node (ref "U4") (pin "41") (pinfunction "RPB5/USBID/RB5_41") (pintype "bidirectional+no_connect"))
    )
    (net (code "87") (name "unconnected-(U4-RPB7{slash}CTED3{slash}PMD5{slash}INT0{slash}RB7-Pad43)") (class "Default")
      (node (ref "U4") (pin "43") (pinfunction "RPB7/CTED3/PMD5/INT0/RB7_43") (pintype "bidirectional+no_connect"))
    )
    (net (code "88") (name "unconnected-(U4-RPC6{slash}PMA1{slash}RC6-Pad2)") (class "Default")
      (node (ref "U4") (pin "2") (pinfunction "RPC6/PMA1/RC6_2") (pintype "bidirectional"))
    )
    (net (code "89") (name "unconnected-(U4-RPC7{slash}PMA0{slash}RC7-Pad3)") (class "Default")
      (node (ref "U4") (pin "3") (pinfunction "RPC7/PMA0/RC7_3") (pintype "bidirectional+no_connect"))
    )
    (net (code "90") (name "unconnected-(U4-RPC9{slash}CTED7{slash}PMA6{slash}RC9-Pad5)") (class "Default")
      (node (ref "U4") (pin "5") (pinfunction "RPC9/CTED7/PMA6/RC9_5") (pintype "bidirectional"))
    )
    (net (code "91") (name "unconnected-(U4-SOSCO{slash}RPA4{slash}T1CK{slash}CTED9{slash}RA4-Pad34)") (class "Default")
      (node (ref "U4") (pin "34") (pinfunction "SOSCO/RPA4/T1CK/CTED9/RA4_34") (pintype "bidirectional+no_connect"))
    )
    (net (code "92") (name "unconnected-(U4-TDI{slash}RPA9{slash}PMA9{slash}RA9-Pad35)") (class "Default")
      (node (ref "U4") (pin "35") (pinfunction "TDI/RPA9/PMA9/RA9_35") (pintype "passive+no_connect"))
    )
    (net (code "93") (name "unconnected-(U4-TDO{slash}RPA8{slash}PMA8{slash}RA8-Pad32)") (class "Default")
      (node (ref "U4") (pin "32") (pinfunction "TDO/RPA8/PMA8/RA8_32") (pintype "passive+no_connect"))
    )
    (net (code "94") (name "unconnected-(U4-VBUS-Pad42)") (class "Default")
      (node (ref "U4") (pin "42") (pinfunction "VBUS_42") (pintype "passive+no_connect"))
    )
  )
)
